# act-drive1.net
KiCad netlist of a schematic drawn in EAGLE
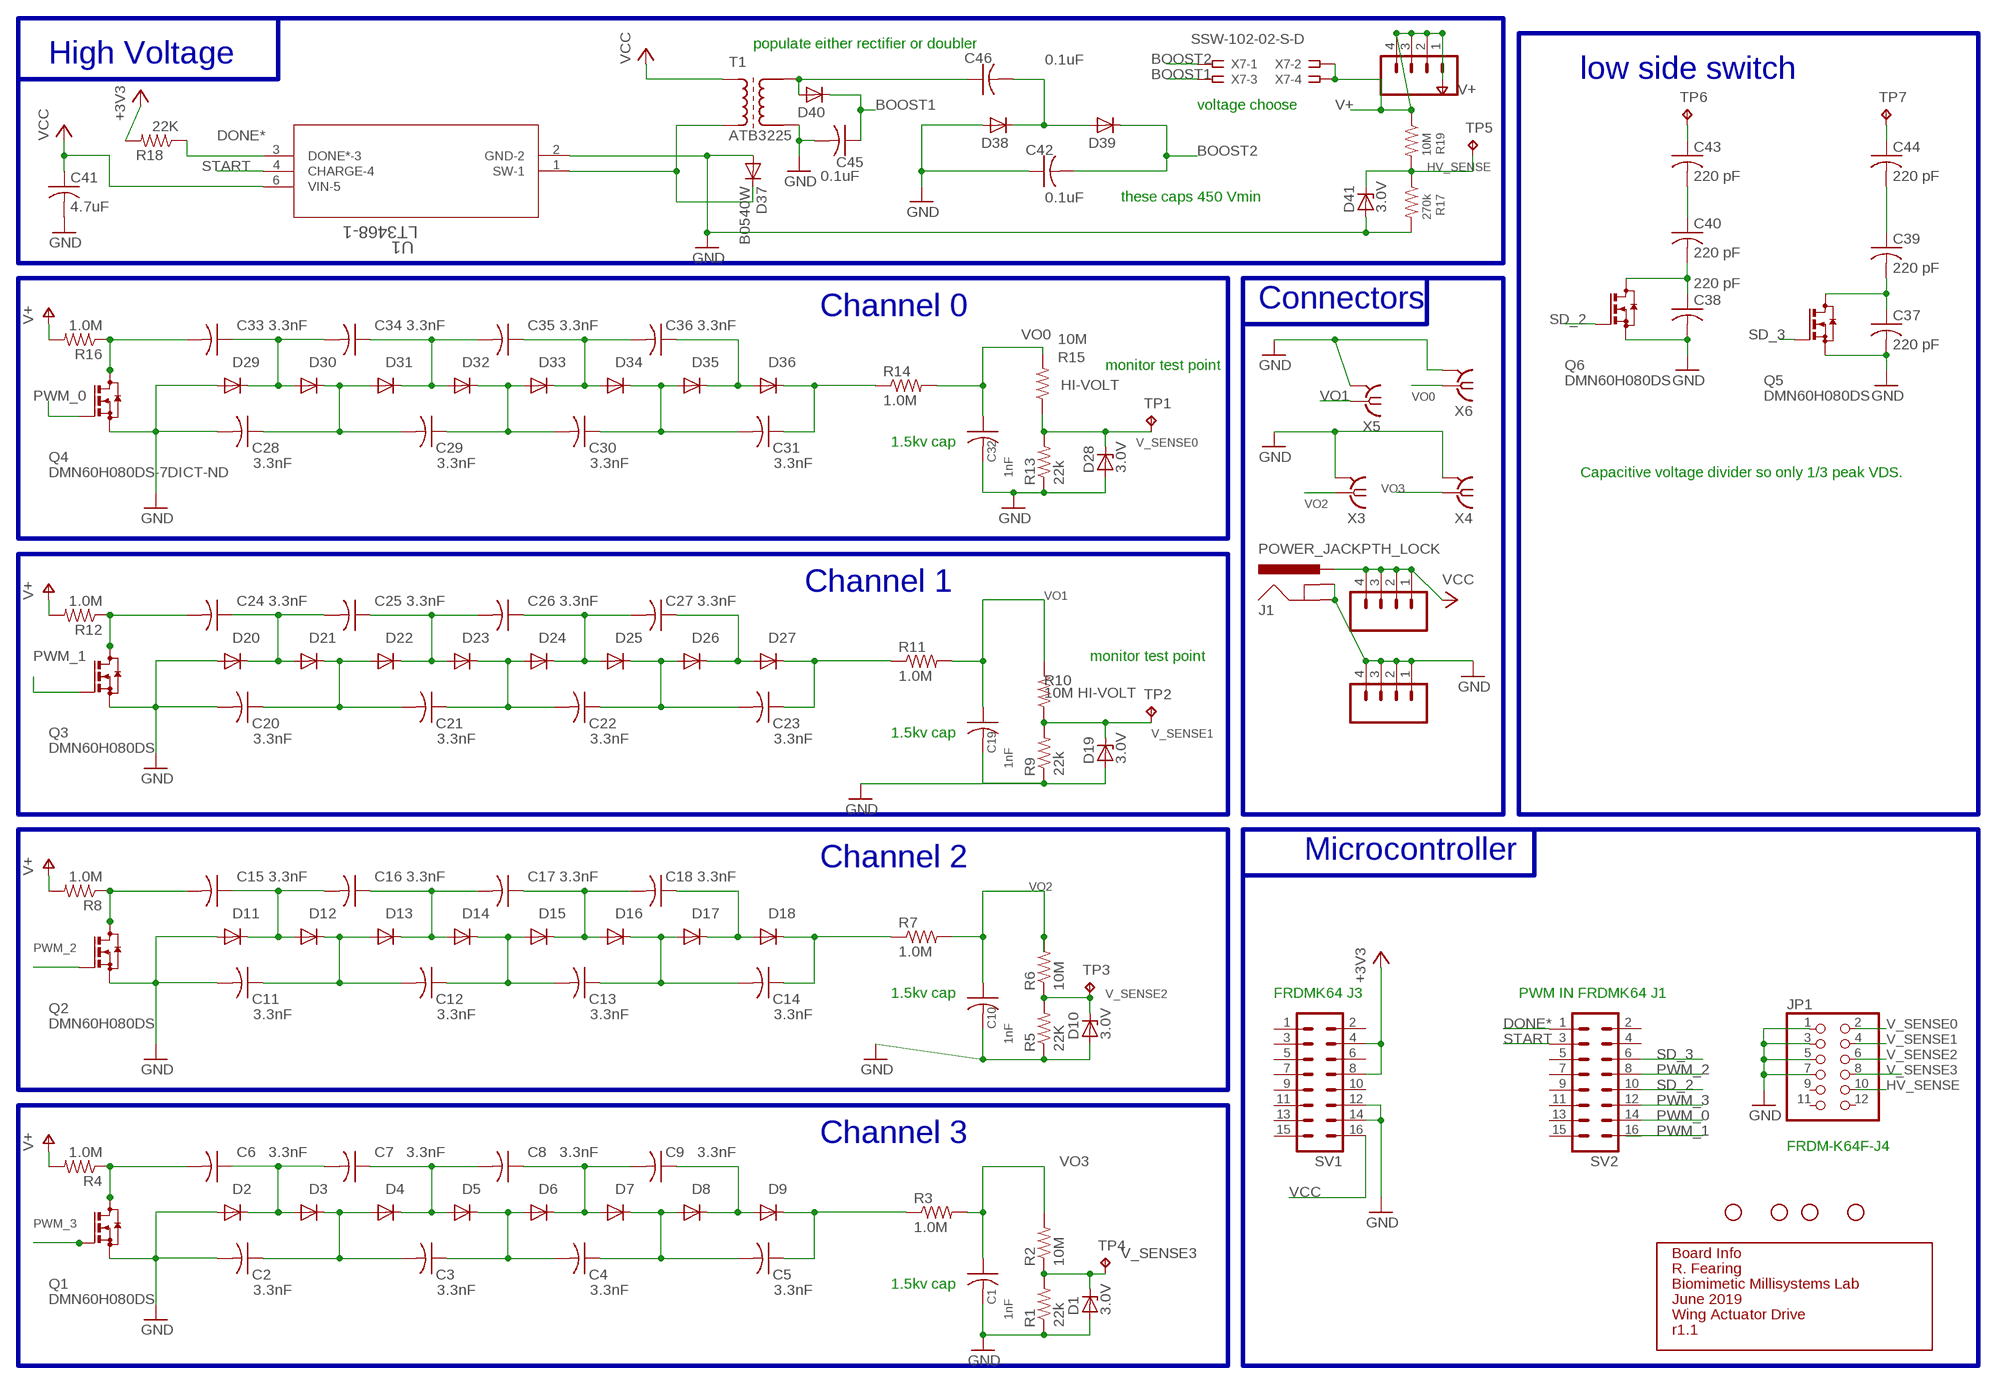
[diagram p0: schematic, sheet 1]

(export (version "E")
  (design (tool "Eeschema 10.0.6"))
  (components
    (comp (ref "C1")
      (value "1nF")
      (footprint "eagle-import:C1206")
      (libsource (lib "eagle-import") (part "C-USC1206"))
    )
    (comp (ref "C2")
      (value "3.3nF")
      (footprint "eagle-import:C0805K")
      (libsource (lib "eagle-import") (part "rcl_334_C-USC0805K"))
    )
    (comp (ref "C3")
      (value "3.3nF")
      (footprint "eagle-import:C0805K")
      (libsource (lib "eagle-import") (part "rcl_334_C-USC0805K"))
    )
    (comp (ref "C4")
      (value "3.3nF")
      (footprint "eagle-import:C0805K")
      (libsource (lib "eagle-import") (part "rcl_334_C-USC0805K"))
    )
    (comp (ref "C5")
      (value "3.3nF")
      (footprint "eagle-import:C0805K")
      (libsource (lib "eagle-import") (part "rcl_334_C-USC0805K"))
    )
    (comp (ref "C6")
      (value "3.3nF")
      (footprint "eagle-import:C0805K")
      (libsource (lib "eagle-import") (part "rcl_334_C-USC0805K"))
    )
    (comp (ref "C7")
      (value "3.3nF")
      (footprint "eagle-import:C0805K")
      (libsource (lib "eagle-import") (part "rcl_334_C-USC0805K"))
    )
    (comp (ref "C8")
      (value "3.3nF")
      (footprint "eagle-import:C0805K")
      (libsource (lib "eagle-import") (part "rcl_334_C-USC0805K"))
    )
    (comp (ref "C9")
      (value "3.3nF")
      (footprint "eagle-import:C0805K")
      (libsource (lib "eagle-import") (part "rcl_334_C-USC0805K"))
    )
    (comp (ref "C10")
      (value "1nF")
      (footprint "eagle-import:C1206")
      (libsource (lib "eagle-import") (part "C-USC1206"))
    )
    (comp (ref "C11")
      (value "3.3nF")
      (footprint "eagle-import:C0805K")
      (libsource (lib "eagle-import") (part "rcl_334_C-USC0805K"))
    )
    (comp (ref "C12")
      (value "3.3nF")
      (footprint "eagle-import:C0805K")
      (libsource (lib "eagle-import") (part "rcl_334_C-USC0805K"))
    )
    (comp (ref "C13")
      (value "3.3nF")
      (footprint "eagle-import:C0805K")
      (libsource (lib "eagle-import") (part "rcl_334_C-USC0805K"))
    )
    (comp (ref "C14")
      (value "3.3nF")
      (footprint "eagle-import:C0805K")
      (libsource (lib "eagle-import") (part "rcl_334_C-USC0805K"))
    )
    (comp (ref "C15")
      (value "3.3nF")
      (footprint "eagle-import:C0805K")
      (libsource (lib "eagle-import") (part "rcl_334_C-USC0805K"))
    )
    (comp (ref "C16")
      (value "3.3nF")
      (footprint "eagle-import:C0805K")
      (libsource (lib "eagle-import") (part "rcl_334_C-USC0805K"))
    )
    (comp (ref "C17")
      (value "3.3nF")
      (footprint "eagle-import:C0805K")
      (libsource (lib "eagle-import") (part "rcl_334_C-USC0805K"))
    )
    (comp (ref "C18")
      (value "3.3nF")
      (footprint "eagle-import:C0805K")
      (libsource (lib "eagle-import") (part "rcl_334_C-USC0805K"))
    )
    (comp (ref "C19")
      (value "1nF")
      (footprint "eagle-import:C1206")
      (libsource (lib "eagle-import") (part "C-USC1206"))
    )
    (comp (ref "C20")
      (value "3.3nF")
      (footprint "eagle-import:C0805K")
      (libsource (lib "eagle-import") (part "rcl_334_C-USC0805K"))
    )
    (comp (ref "C21")
      (value "3.3nF")
      (footprint "eagle-import:C0805K")
      (libsource (lib "eagle-import") (part "rcl_334_C-USC0805K"))
    )
    (comp (ref "C22")
      (value "3.3nF")
      (footprint "eagle-import:C0805K")
      (libsource (lib "eagle-import") (part "rcl_334_C-USC0805K"))
    )
    (comp (ref "C23")
      (value "3.3nF")
      (footprint "eagle-import:C0805K")
      (libsource (lib "eagle-import") (part "rcl_334_C-USC0805K"))
    )
    (comp (ref "C24")
      (value "3.3nF")
      (footprint "eagle-import:C0805K")
      (libsource (lib "eagle-import") (part "rcl_334_C-USC0805K"))
    )
    (comp (ref "C25")
      (value "3.3nF")
      (footprint "eagle-import:C0805K")
      (libsource (lib "eagle-import") (part "rcl_334_C-USC0805K"))
    )
    (comp (ref "C26")
      (value "3.3nF")
      (footprint "eagle-import:C0805K")
      (libsource (lib "eagle-import") (part "rcl_334_C-USC0805K"))
    )
    (comp (ref "C27")
      (value "3.3nF")
      (footprint "eagle-import:C0805K")
      (libsource (lib "eagle-import") (part "rcl_334_C-USC0805K"))
    )
    (comp (ref "C28")
      (value "3.3nF")
      (footprint "eagle-import:C0805K")
      (libsource (lib "eagle-import") (part "rcl_334_C-USC0805K"))
    )
    (comp (ref "C29")
      (value "3.3nF")
      (footprint "eagle-import:C0805K")
      (libsource (lib "eagle-import") (part "rcl_334_C-USC0805K"))
    )
    (comp (ref "C30")
      (value "3.3nF")
      (footprint "eagle-import:C0805K")
      (libsource (lib "eagle-import") (part "rcl_334_C-USC0805K"))
    )
    (comp (ref "C31")
      (value "3.3nF")
      (footprint "eagle-import:C0805K")
      (libsource (lib "eagle-import") (part "rcl_334_C-USC0805K"))
    )
    (comp (ref "C32")
      (value "1nF")
      (footprint "eagle-import:C1206")
      (libsource (lib "eagle-import") (part "C-USC1206"))
    )
    (comp (ref "C33")
      (value "3.3nF")
      (footprint "eagle-import:C0805K")
      (libsource (lib "eagle-import") (part "rcl_334_C-USC0805K"))
    )
    (comp (ref "C34")
      (value "3.3nF")
      (footprint "eagle-import:C0805K")
      (libsource (lib "eagle-import") (part "rcl_334_C-USC0805K"))
    )
    (comp (ref "C35")
      (value "3.3nF")
      (footprint "eagle-import:C0805K")
      (libsource (lib "eagle-import") (part "rcl_334_C-USC0805K"))
    )
    (comp (ref "C36")
      (value "3.3nF")
      (footprint "eagle-import:C0805K")
      (libsource (lib "eagle-import") (part "rcl_334_C-USC0805K"))
    )
    (comp (ref "C37")
      (value "220 pF")
      (footprint "eagle-import:C1206")
      (libsource (lib "eagle-import") (part "rcl_334_C-USC1206"))
    )
    (comp (ref "C38")
      (value "220 pF")
      (footprint "eagle-import:C1206")
      (libsource (lib "eagle-import") (part "rcl_334_C-USC1206"))
    )
    (comp (ref "C39")
      (value "220 pF")
      (footprint "eagle-import:C1206")
      (libsource (lib "eagle-import") (part "rcl_334_C-USC1206"))
    )
    (comp (ref "C40")
      (value "220 pF")
      (footprint "eagle-import:C1206")
      (libsource (lib "eagle-import") (part "rcl_334_C-USC1206"))
    )
    (comp (ref "C41")
      (value "4.7uF")
      (footprint "eagle-import:C1206")
      (libsource (lib "eagle-import") (part "C-USC1206"))
    )
    (comp (ref "C42")
      (value "0.1uF")
      (footprint "eagle-import:C1206")
      (libsource (lib "eagle-import") (part "rcl_334_C-USC1206"))
    )
    (comp (ref "C43")
      (value "220 pF")
      (footprint "eagle-import:C1206")
      (libsource (lib "eagle-import") (part "rcl_334_C-USC1206"))
    )
    (comp (ref "C44")
      (value "220 pF")
      (footprint "eagle-import:C1206")
      (libsource (lib "eagle-import") (part "rcl_334_C-USC1206"))
    )
    (comp (ref "C45")
      (value "0.1uF")
      (footprint "eagle-import:C1206")
      (libsource (lib "eagle-import") (part "rcl_334_C-USC1206"))
    )
    (comp (ref "C46")
      (value "0.1uF")
      (footprint "eagle-import:C1206")
      (libsource (lib "eagle-import") (part "rcl_334_C-USC1206"))
    )
    (comp (ref "D1")
      (value "3.0V")
      (footprint "eagle-import:SOD80C")
      (libsource (lib "eagle-import") (part "ZENER-DIODESOD80C"))
    )
    (comp (ref "D2")
      (value "DIODE-SOD323-W")
      (footprint "eagle-import:SOD323-W")
      (libsource (lib "eagle-import") (part "DIODE-SOD323-W"))
    )
    (comp (ref "D3")
      (value "DIODE-SOD323-W")
      (footprint "eagle-import:SOD323-W")
      (libsource (lib "eagle-import") (part "DIODE-SOD323-W"))
    )
    (comp (ref "D4")
      (value "DIODE-SOD323-W")
      (footprint "eagle-import:SOD323-W")
      (libsource (lib "eagle-import") (part "DIODE-SOD323-W"))
    )
    (comp (ref "D5")
      (value "DIODE-SOD323-W")
      (footprint "eagle-import:SOD323-W")
      (libsource (lib "eagle-import") (part "DIODE-SOD323-W"))
    )
    (comp (ref "D6")
      (value "DIODE-SOD323-W")
      (footprint "eagle-import:SOD323-W")
      (libsource (lib "eagle-import") (part "DIODE-SOD323-W"))
    )
    (comp (ref "D7")
      (value "DIODE-SOD323-W")
      (footprint "eagle-import:SOD323-W")
      (libsource (lib "eagle-import") (part "DIODE-SOD323-W"))
    )
    (comp (ref "D8")
      (value "DIODE-SOD323-W")
      (footprint "eagle-import:SOD323-W")
      (libsource (lib "eagle-import") (part "DIODE-SOD323-W"))
    )
    (comp (ref "D9")
      (value "DIODE-SOD323-W")
      (footprint "eagle-import:SOD323-W")
      (libsource (lib "eagle-import") (part "DIODE-SOD323-W"))
    )
    (comp (ref "D10")
      (value "3.0V")
      (footprint "eagle-import:SOD80C")
      (libsource (lib "eagle-import") (part "ZENER-DIODESOD80C"))
    )
    (comp (ref "D11")
      (value "DIODE-SOD323-W")
      (footprint "eagle-import:SOD323-W")
      (libsource (lib "eagle-import") (part "DIODE-SOD323-W"))
    )
    (comp (ref "D12")
      (value "DIODE-SOD323-W")
      (footprint "eagle-import:SOD323-W")
      (libsource (lib "eagle-import") (part "DIODE-SOD323-W"))
    )
    (comp (ref "D13")
      (value "DIODE-SOD323-W")
      (footprint "eagle-import:SOD323-W")
      (libsource (lib "eagle-import") (part "DIODE-SOD323-W"))
    )
    (comp (ref "D14")
      (value "DIODE-SOD323-W")
      (footprint "eagle-import:SOD323-W")
      (libsource (lib "eagle-import") (part "DIODE-SOD323-W"))
    )
    (comp (ref "D15")
      (value "DIODE-SOD323-W")
      (footprint "eagle-import:SOD323-W")
      (libsource (lib "eagle-import") (part "DIODE-SOD323-W"))
    )
    (comp (ref "D16")
      (value "DIODE-SOD323-W")
      (footprint "eagle-import:SOD323-W")
      (libsource (lib "eagle-import") (part "DIODE-SOD323-W"))
    )
    (comp (ref "D17")
      (value "DIODE-SOD323-W")
      (footprint "eagle-import:SOD323-W")
      (libsource (lib "eagle-import") (part "DIODE-SOD323-W"))
    )
    (comp (ref "D18")
      (value "DIODE-SOD323-W")
      (footprint "eagle-import:SOD323-W")
      (libsource (lib "eagle-import") (part "DIODE-SOD323-W"))
    )
    (comp (ref "D19")
      (value "3.0V")
      (footprint "eagle-import:SOD80C")
      (libsource (lib "eagle-import") (part "ZENER-DIODESOD80C"))
    )
    (comp (ref "D20")
      (value "DIODE-SOD323-W")
      (footprint "eagle-import:SOD323-W")
      (libsource (lib "eagle-import") (part "DIODE-SOD323-W"))
    )
    (comp (ref "D21")
      (value "DIODE-SOD323-W")
      (footprint "eagle-import:SOD323-W")
      (libsource (lib "eagle-import") (part "DIODE-SOD323-W"))
    )
    (comp (ref "D22")
      (value "DIODE-SOD323-W")
      (footprint "eagle-import:SOD323-W")
      (libsource (lib "eagle-import") (part "DIODE-SOD323-W"))
    )
    (comp (ref "D23")
      (value "DIODE-SOD323-W")
      (footprint "eagle-import:SOD323-W")
      (libsource (lib "eagle-import") (part "DIODE-SOD323-W"))
    )
    (comp (ref "D24")
      (value "DIODE-SOD323-W")
      (footprint "eagle-import:SOD323-W")
      (libsource (lib "eagle-import") (part "DIODE-SOD323-W"))
    )
    (comp (ref "D25")
      (value "DIODE-SOD323-W")
      (footprint "eagle-import:SOD323-W")
      (libsource (lib "eagle-import") (part "DIODE-SOD323-W"))
    )
    (comp (ref "D26")
      (value "DIODE-SOD323-W")
      (footprint "eagle-import:SOD323-W")
      (libsource (lib "eagle-import") (part "DIODE-SOD323-W"))
    )
    (comp (ref "D27")
      (value "DIODE-SOD323-W")
      (footprint "eagle-import:SOD323-W")
      (libsource (lib "eagle-import") (part "DIODE-SOD323-W"))
    )
    (comp (ref "D28")
      (value "3.0V")
      (footprint "eagle-import:SOD80C")
      (libsource (lib "eagle-import") (part "ZENER-DIODESOD80C"))
    )
    (comp (ref "D29")
      (value "DIODE-SOD323-W")
      (footprint "eagle-import:SOD323-W")
      (libsource (lib "eagle-import") (part "DIODE-SOD323-W"))
    )
    (comp (ref "D30")
      (value "DIODE-SOD323-W")
      (footprint "eagle-import:SOD323-W")
      (libsource (lib "eagle-import") (part "DIODE-SOD323-W"))
    )
    (comp (ref "D31")
      (value "DIODE-SOD323-W")
      (footprint "eagle-import:SOD323-W")
      (libsource (lib "eagle-import") (part "DIODE-SOD323-W"))
    )
    (comp (ref "D32")
      (value "DIODE-SOD323-W")
      (footprint "eagle-import:SOD323-W")
      (libsource (lib "eagle-import") (part "DIODE-SOD323-W"))
    )
    (comp (ref "D33")
      (value "DIODE-SOD323-W")
      (footprint "eagle-import:SOD323-W")
      (libsource (lib "eagle-import") (part "DIODE-SOD323-W"))
    )
    (comp (ref "D34")
      (value "DIODE-SOD323-W")
      (footprint "eagle-import:SOD323-W")
      (libsource (lib "eagle-import") (part "DIODE-SOD323-W"))
    )
    (comp (ref "D35")
      (value "DIODE-SOD323-W")
      (footprint "eagle-import:SOD323-W")
      (libsource (lib "eagle-import") (part "DIODE-SOD323-W"))
    )
    (comp (ref "D36")
      (value "DIODE-SOD323-W")
      (footprint "eagle-import:SOD323-W")
      (libsource (lib "eagle-import") (part "DIODE-SOD323-W"))
    )
    (comp (ref "D37")
      (value "B0540W")
      (footprint "eagle-import:SOD123")
      (libsource (lib "eagle-import") (part "DIODE-SOD123"))
    )
    (comp (ref "D38")
      (value "DIODE-SOD323-W")
      (footprint "eagle-import:SOD323-W")
      (libsource (lib "eagle-import") (part "DIODE-SOD323-W"))
    )
    (comp (ref "D39")
      (value "DIODE-SOD323-W")
      (footprint "eagle-import:SOD323-W")
      (libsource (lib "eagle-import") (part "DIODE-SOD323-W"))
    )
    (comp (ref "D40")
      (value "DIODE-SOD323-W")
      (footprint "eagle-import:SOD323-W")
      (libsource (lib "eagle-import") (part "DIODE-SOD323-W"))
    )
    (comp (ref "D41")
      (value "3.0V")
      (footprint "eagle-import:SOD80C")
      (libsource (lib "eagle-import") (part "ZENER-DIODESOD80C"))
    )
    (comp (ref "H1")
      (value "STAND-OFFTIGHT")
      (footprint "eagle-import:STAND-OFF-TIGHT")
      (libsource (lib "eagle-import") (part "STAND-OFFTIGHT"))
    )
    (comp (ref "H2")
      (value "STAND-OFFTIGHT")
      (footprint "eagle-import:STAND-OFF-TIGHT")
      (libsource (lib "eagle-import") (part "STAND-OFFTIGHT"))
    )
    (comp (ref "H3")
      (value "STAND-OFFTIGHT")
      (footprint "eagle-import:STAND-OFF-TIGHT")
      (libsource (lib "eagle-import") (part "STAND-OFFTIGHT"))
    )
    (comp (ref "H4")
      (value "STAND-OFFTIGHT")
      (footprint "eagle-import:STAND-OFF-TIGHT")
      (libsource (lib "eagle-import") (part "STAND-OFFTIGHT"))
    )
    (comp (ref "I1")
      (value "INFO")
      (footprint "eagle-import:INFO")
      (fields
        (field (name "AUTHOR") "R. Fearing")
        (field (name "DATE") "June 2019")
        (field (name "DESIGN") "Wing Actuator Drive")
        (field (name "ORGANIZATION") "Biomimetic Millisystems Lab")
        (field (name "REVISION") "r1.1")
      )
      (libsource (lib "eagle-import") (part "INFO"))
    )
    (comp (ref "J1")
      (value "POWER_JACKPTH_LOCK")
      (footprint "eagle-import:POWER_JACK_PTH_LOCK")
      (libsource (lib "eagle-import") (part "POWER_JACKPTH_LOCK"))
    )
    (comp (ref "JP1")
      (value "PINHD-2X6")
      (footprint "eagle-import:2X06")
      (libsource (lib "eagle-import") (part "PINHD-2X6"))
    )
    (comp (ref "JP2")
      (value "M04LOCK")
      (footprint "eagle-import:1X04_LOCK")
      (libsource (lib "eagle-import") (part "M04LOCK"))
    )
    (comp (ref "JP3")
      (value "M04LOCK")
      (footprint "eagle-import:1X04_LOCK")
      (libsource (lib "eagle-import") (part "M04LOCK"))
    )
    (comp (ref "JP4")
      (value "M04LOCK")
      (footprint "eagle-import:1X04_LOCK")
      (libsource (lib "eagle-import") (part "M04LOCK"))
    )
    (comp (ref "Q1")
      (value "BSS123")
      (footprint "eagle-import:SOT23")
      (fields (field (name "PART#") "DMN60H080DS"))
      (libsource (lib "eagle-import") (part "BSS123"))
    )
    (comp (ref "Q2")
      (value "BSS123")
      (footprint "eagle-import:SOT23")
      (fields (field (name "PART#") "DMN60H080DS"))
      (libsource (lib "eagle-import") (part "BSS123"))
    )
    (comp (ref "Q3")
      (value "BSS123")
      (footprint "eagle-import:SOT23")
      (fields (field (name "PART#") "DMN60H080DS"))
      (libsource (lib "eagle-import") (part "BSS123"))
    )
    (comp (ref "Q4")
      (value "BSS123")
      (footprint "eagle-import:SOT23")
      (fields (field (name "DIGIKEY") "DMN60H080DS-7DICT-ND "))
      (libsource (lib "eagle-import") (part "BSS123"))
    )
    (comp (ref "Q5")
      (value "BSS123")
      (footprint "eagle-import:SOT23")
      (fields (field (name "PART#") "DMN60H080DS"))
      (libsource (lib "eagle-import") (part "BSS123"))
    )
    (comp (ref "Q6")
      (value "BSS123")
      (footprint "eagle-import:SOT23")
      (fields (field (name "PART#") "DMN60H080DS"))
      (libsource (lib "eagle-import") (part "BSS123"))
    )
    (comp (ref "R1")
      (value "22k")
      (footprint "eagle-import:R1206")
      (libsource (lib "eagle-import") (part "R-US_R1206"))
    )
    (comp (ref "R2")
      (value "10M")
      (footprint "eagle-import:R2010")
      (libsource (lib "eagle-import") (part "R-US_R2010"))
    )
    (comp (ref "R3")
      (value "1.0M")
      (footprint "eagle-import:R1206")
      (libsource (lib "eagle-import") (part "R-US_R1206"))
    )
    (comp (ref "R4")
      (value "1.0M")
      (footprint "eagle-import:R1206")
      (libsource (lib "eagle-import") (part "R-US_R1206"))
    )
    (comp (ref "R5")
      (value "22K")
      (footprint "eagle-import:R1206")
      (libsource (lib "eagle-import") (part "R-US_R1206"))
    )
    (comp (ref "R6")
      (value "10M")
      (footprint "eagle-import:R2010")
      (libsource (lib "eagle-import") (part "R-US_R2010"))
    )
    (comp (ref "R7")
      (value "1.0M")
      (footprint "eagle-import:R1206")
      (libsource (lib "eagle-import") (part "R-US_R1206"))
    )
    (comp (ref "R8")
      (value "1.0M")
      (footprint "eagle-import:R1206")
      (libsource (lib "eagle-import") (part "R-US_R1206"))
    )
    (comp (ref "R9")
      (value "22k")
      (footprint "eagle-import:R1206")
      (libsource (lib "eagle-import") (part "R-US_R1206"))
    )
    (comp (ref "R10")
      (value "10M")
      (footprint "eagle-import:R2010")
      (libsource (lib "eagle-import") (part "R-US_R2010"))
    )
    (comp (ref "R11")
      (value "1.0M")
      (footprint "eagle-import:R1206")
      (libsource (lib "eagle-import") (part "R-US_R1206"))
    )
    (comp (ref "R12")
      (value "1.0M")
      (footprint "eagle-import:R1206")
      (libsource (lib "eagle-import") (part "R-US_R1206"))
    )
    (comp (ref "R13")
      (value "22k")
      (footprint "eagle-import:R1206")
      (libsource (lib "eagle-import") (part "R-US_R1206"))
    )
    (comp (ref "R14")
      (value "1.0M")
      (footprint "eagle-import:R1206")
      (libsource (lib "eagle-import") (part "R-US_R1206"))
    )
    (comp (ref "R15")
      (value "10M")
      (footprint "eagle-import:R2010")
      (libsource (lib "eagle-import") (part "R-US_R2010"))
    )
    (comp (ref "R16")
      (value "1.0M")
      (footprint "eagle-import:R1206")
      (libsource (lib "eagle-import") (part "R-US_R1206"))
    )
    (comp (ref "R17")
      (value "270k")
      (footprint "eagle-import:R1206")
      (libsource (lib "eagle-import") (part "R-US_R1206"))
    )
    (comp (ref "R18")
      (value "22K")
      (footprint "eagle-import:R1206")
      (libsource (lib "eagle-import") (part "resistor_348_R-US_R1206"))
    )
    (comp (ref "R19")
      (value "10M")
      (footprint "eagle-import:R1206")
      (libsource (lib "eagle-import") (part "R-US_R1206"))
    )
    (comp (ref "SV1")
      (value "ML16")
      (footprint "eagle-import:ML16")
      (libsource (lib "eagle-import") (part "ML16"))
    )
    (comp (ref "SV2")
      (value "ML16")
      (footprint "eagle-import:ML16")
      (libsource (lib "eagle-import") (part "ML16"))
    )
    (comp (ref "T1")
      (value "ATB3225")
      (footprint "eagle-import:XFMR3225")
      (libsource (lib "eagle-import") (part "ATB3225"))
    )
    (comp (ref "TP1")
      (value "TPTP10SQ")
      (footprint "eagle-import:TP10SQ")
      (libsource (lib "eagle-import") (part "TPTP10SQ"))
    )
    (comp (ref "TP2")
      (value "TPTP10SQ")
      (footprint "eagle-import:TP10SQ")
      (libsource (lib "eagle-import") (part "TPTP10SQ"))
    )
    (comp (ref "TP3")
      (value "TPTP10SQ")
      (footprint "eagle-import:TP10SQ")
      (libsource (lib "eagle-import") (part "TPTP10SQ"))
    )
    (comp (ref "TP4")
      (value "TPTP10SQ")
      (footprint "eagle-import:TP10SQ")
      (libsource (lib "eagle-import") (part "TPTP10SQ"))
    )
    (comp (ref "TP5")
      (value "TPTP20SQ")
      (footprint "eagle-import:TP20SQ")
      (libsource (lib "eagle-import") (part "TPTP20SQ"))
    )
    (comp (ref "TP6")
      (value "TPTP20SQ")
      (footprint "eagle-import:TP20SQ")
      (libsource (lib "eagle-import") (part "TPTP20SQ"))
    )
    (comp (ref "TP7")
      (value "TPTP20SQ")
      (footprint "eagle-import:TP20SQ")
      (libsource (lib "eagle-import") (part "TPTP20SQ"))
    )
    (comp (ref "U1")
      (value "LT3468-1")
      (footprint "eagle-import:TSOT-23_S5")
      (libsource (lib "eagle-import") (part "LT3468-1"))
    )
    (comp (ref "X3")
      (value "SMA-142-0701-801/806")
      (footprint "eagle-import:J502-ND-142-0701-801_806")
      (fields (field (name "MF") "JOHNSON COMPONENTS") (field (name "MPN") "142-0701-801"))
      (libsource (lib "eagle-import") (part "SMA-142-0701-801/806"))
    )
    (comp (ref "X4")
      (value "SMA-142-0701-801/806")
      (footprint "eagle-import:J502-ND-142-0701-801_806")
      (fields (field (name "MF") "JOHNSON COMPONENTS") (field (name "MPN") "142-0701-801"))
      (libsource (lib "eagle-import") (part "SMA-142-0701-801/806"))
    )
    (comp (ref "X5")
      (value "SMA-142-0701-801/806")
      (footprint "eagle-import:J502-ND-142-0701-801_806")
      (fields (field (name "MF") "JOHNSON COMPONENTS") (field (name "MPN") "142-0701-801"))
      (libsource (lib "eagle-import") (part "SMA-142-0701-801/806"))
    )
    (comp (ref "X6")
      (value "SMA-142-0701-801/806")
      (footprint "eagle-import:J502-ND-142-0701-801_806")
      (fields (field (name "MF") "JOHNSON COMPONENTS") (field (name "MPN") "142-0701-801"))
      (libsource (lib "eagle-import") (part "SMA-142-0701-801/806"))
    )
    (comp (ref "X7")
      (value "SSW-102-02-S-D")
      (footprint "eagle-import:SSW-102-02-S-D")
      (libsource (lib "eagle-import") (part "SSW-102-02-S-D"))
    )
  )
  (nets
    (net (code "3") (name "+3V3") (class "Default")
      (node (ref "R18") (pin "2") (pinfunction "2_2") (pintype "passive"))
      (node (ref "SV1") (pin "4") (pinfunction "4_4") (pintype "passive"))
      (node (ref "SV1") (pin "8") (pinfunction "8_8") (pintype "passive"))
    )
    (net (code "4") (name "/BOOST1") (class "Default")
      (node (ref "C45") (pin "1") (pinfunction "1_1") (pintype "passive"))
      (node (ref "D40") (pin "C") (pinfunction "C_C") (pintype "passive"))
      (node (ref "X7") (pin "3") (pinfunction "1_3") (pintype "passive"))
    )
    (net (code "5") (name "/BOOST2") (class "Default")
      (node (ref "C42") (pin "2") (pinfunction "2_2") (pintype "passive"))
      (node (ref "D39") (pin "C") (pinfunction "C_C") (pintype "passive"))
      (node (ref "X7") (pin "1") (pinfunction "1_1") (pintype "passive"))
    )
    (net (code "6") (name "/DONE*") (class "Default")
      (node (ref "R18") (pin "1") (pinfunction "1_1") (pintype "passive"))
      (node (ref "SV2") (pin "1") (pinfunction "1_1") (pintype "passive"))
      (node (ref "U1") (pin "3") (pinfunction "DONE*-3_3") (pintype "passive"))
    )
    (net (code "7") (name "/HV_SENSE") (class "Default")
      (node (ref "D41") (pin "C") (pinfunction "C_C") (pintype "passive"))
      (node (ref "JP1") (pin "10") (pinfunction "10_10") (pintype "passive"))
      (node (ref "R17") (pin "1") (pinfunction "1_1") (pintype "passive"))
      (node (ref "R19") (pin "2") (pinfunction "2_2") (pintype "passive"))
      (node (ref "TP5") (pin "TP") (pinfunction "TP_TP") (pintype "input"))
    )
    (net (code "8") (name "/PWM_0") (class "Default")
      (node (ref "Q4") (pin "1") (pinfunction "G_1") (pintype "passive"))
      (node (ref "SV2") (pin "14") (pinfunction "14_14") (pintype "passive"))
    )
    (net (code "9") (name "/PWM_1") (class "Default")
      (node (ref "Q3") (pin "1") (pinfunction "G_1") (pintype "passive"))
      (node (ref "SV2") (pin "16") (pinfunction "16_16") (pintype "passive"))
    )
    (net (code "10") (name "/PWM_2") (class "Default")
      (node (ref "Q2") (pin "1") (pinfunction "G_1") (pintype "passive"))
      (node (ref "SV2") (pin "8") (pinfunction "8_8") (pintype "passive"))
    )
    (net (code "11") (name "/PWM_3") (class "Default")
      (node (ref "Q1") (pin "1") (pinfunction "G_1") (pintype "passive"))
      (node (ref "SV2") (pin "12") (pinfunction "12_12") (pintype "passive"))
    )
    (net (code "12") (name "/SD_2") (class "Default")
      (node (ref "Q6") (pin "1") (pinfunction "G_1") (pintype "passive"))
      (node (ref "SV2") (pin "10") (pinfunction "10_10") (pintype "passive"))
    )
    (net (code "13") (name "/SD_3") (class "Default")
      (node (ref "Q5") (pin "1") (pinfunction "G_1") (pintype "passive"))
      (node (ref "SV2") (pin "6") (pinfunction "6_6") (pintype "passive"))
    )
    (net (code "14") (name "/START") (class "Default")
      (node (ref "SV2") (pin "3") (pinfunction "3_3") (pintype "passive"))
      (node (ref "U1") (pin "4") (pinfunction "CHARGE-4_4") (pintype "passive"))
    )
    (net (code "15") (name "/VO0") (class "Default")
      (node (ref "C32") (pin "1") (pinfunction "1_1") (pintype "passive"))
      (node (ref "R14") (pin "2") (pinfunction "2_2") (pintype "passive"))
      (node (ref "R15") (pin "2") (pinfunction "2_2") (pintype "passive"))
      (node (ref "X6") (pin "1") (pinfunction "1_1") (pintype "passive"))
    )
    (net (code "16") (name "/VO1") (class "Default")
      (node (ref "C19") (pin "1") (pinfunction "1_1") (pintype "passive"))
      (node (ref "R10") (pin "2") (pinfunction "2_2") (pintype "passive"))
      (node (ref "R11") (pin "2") (pinfunction "2_2") (pintype "passive"))
      (node (ref "X5") (pin "1") (pinfunction "1_1") (pintype "passive"))
    )
    (net (code "17") (name "/VO2") (class "Default")
      (node (ref "C10") (pin "1") (pinfunction "1_1") (pintype "passive"))
      (node (ref "R6") (pin "2") (pinfunction "2_2") (pintype "passive"))
      (node (ref "R7") (pin "2") (pinfunction "2_2") (pintype "passive"))
      (node (ref "X3") (pin "1") (pinfunction "1_1") (pintype "passive"))
    )
    (net (code "18") (name "/VO3") (class "Default")
      (node (ref "C1") (pin "1") (pinfunction "1_1") (pintype "passive"))
      (node (ref "R2") (pin "2") (pinfunction "2_2") (pintype "passive"))
      (node (ref "R3") (pin "2") (pinfunction "2_2") (pintype "passive"))
      (node (ref "X4") (pin "1") (pinfunction "1_1") (pintype "passive"))
    )
    (net (code "19") (name "/V_SENSE0") (class "Default")
      (node (ref "D28") (pin "C") (pinfunction "C_C") (pintype "passive"))
      (node (ref "JP1") (pin "2") (pinfunction "2_2") (pintype "passive"))
      (node (ref "R13") (pin "2") (pinfunction "2_2") (pintype "passive"))
      (node (ref "R15") (pin "1") (pinfunction "1_1") (pintype "passive"))
      (node (ref "TP1") (pin "TP") (pinfunction "TP_TP") (pintype "input"))
    )
    (net (code "20") (name "/V_SENSE1") (class "Default")
      (node (ref "D19") (pin "C") (pinfunction "C_C") (pintype "passive"))
      (node (ref "JP1") (pin "4") (pinfunction "4_4") (pintype "passive"))
      (node (ref "R10") (pin "1") (pinfunction "1_1") (pintype "passive"))
      (node (ref "R9") (pin "2") (pinfunction "2_2") (pintype "passive"))
      (node (ref "TP2") (pin "TP") (pinfunction "TP_TP") (pintype "input"))
    )
    (net (code "21") (name "/V_SENSE2") (class "Default")
      (node (ref "D10") (pin "C") (pinfunction "C_C") (pintype "passive"))
      (node (ref "JP1") (pin "6") (pinfunction "6_6") (pintype "passive"))
      (node (ref "R5") (pin "2") (pinfunction "2_2") (pintype "passive"))
      (node (ref "R6") (pin "1") (pinfunction "1_1") (pintype "passive"))
      (node (ref "TP3") (pin "TP") (pinfunction "TP_TP") (pintype "input"))
    )
    (net (code "22") (name "/V_SENSE3") (class "Default")
      (node (ref "D1") (pin "C") (pinfunction "C_C") (pintype "passive"))
      (node (ref "JP1") (pin "8") (pinfunction "8_8") (pintype "passive"))
      (node (ref "R1") (pin "2") (pinfunction "2_2") (pintype "passive"))
      (node (ref "R2") (pin "1") (pinfunction "1_1") (pintype "passive"))
      (node (ref "TP4") (pin "TP") (pinfunction "TP_TP") (pintype "input"))
    )
    (net (code "25") (name "GND") (class "Default")
      (node (ref "C1") (pin "2") (pinfunction "2_2") (pintype "passive"))
      (node (ref "C10") (pin "2") (pinfunction "2_2") (pintype "passive"))
      (node (ref "C11") (pin "2") (pinfunction "2_2") (pintype "passive"))
      (node (ref "C19") (pin "2") (pinfunction "2_2") (pintype "passive"))
      (node (ref "C2") (pin "2") (pinfunction "2_2") (pintype "passive"))
      (node (ref "C20") (pin "2") (pinfunction "2_2") (pintype "passive"))
      (node (ref "C28") (pin "2") (pinfunction "2_2") (pintype "passive"))
      (node (ref "C32") (pin "2") (pinfunction "2_2") (pintype "passive"))
      (node (ref "C37") (pin "2") (pinfunction "2_2") (pintype "passive"))
      (node (ref "C38") (pin "2") (pinfunction "2_2") (pintype "passive"))
      (node (ref "C41") (pin "2") (pinfunction "2_2") (pintype "passive"))
      (node (ref "C42") (pin "1") (pinfunction "1_1") (pintype "passive"))
      (node (ref "C45") (pin "2") (pinfunction "2_2") (pintype "passive"))
      (node (ref "D1") (pin "A") (pinfunction "A_A") (pintype "passive"))
      (node (ref "D10") (pin "A") (pinfunction "A_A") (pintype "passive"))
      (node (ref "D11") (pin "A") (pinfunction "A_A") (pintype "passive"))
      (node (ref "D19") (pin "A") (pinfunction "A_A") (pintype "passive"))
      (node (ref "D2") (pin "A") (pinfunction "A_A") (pintype "passive"))
      (node (ref "D20") (pin "A") (pinfunction "A_A") (pintype "passive"))
      (node (ref "D28") (pin "A") (pinfunction "A_A") (pintype "passive"))
      (node (ref "D29") (pin "A") (pinfunction "A_A") (pintype "passive"))
      (node (ref "D37") (pin "A") (pinfunction "A_A") (pintype "passive"))
      (node (ref "D38") (pin "A") (pinfunction "A_A") (pintype "passive"))
      (node (ref "D41") (pin "A") (pinfunction "A_A") (pintype "passive"))
      (node (ref "J1") (pin "GND") (pinfunction "GND_GND") (pintype "bidirectional"))
      (node (ref "J1") (pin "GNDBREAK") (pinfunction "GNDBREAK_GNDBREAK") (pintype "bidirectional"))
      (node (ref "JP1") (pin "1") (pinfunction "1_1") (pintype "passive"))
      (node (ref "JP1") (pin "3") (pinfunction "3_3") (pintype "passive"))
      (node (ref "JP1") (pin "5") (pinfunction "5_5") (pintype "passive"))
      (node (ref "JP1") (pin "7") (pinfunction "7_7") (pintype "passive"))
      (node (ref "JP2") (pin "1") (pinfunction "1_1") (pintype "passive"))
      (node (ref "JP2") (pin "2") (pinfunction "2_2") (pintype "passive"))
      (node (ref "JP2") (pin "3") (pinfunction "3_3") (pintype "passive"))
      (node (ref "JP2") (pin "4") (pinfunction "4_4") (pintype "passive"))
      (node (ref "Q1") (pin "2") (pinfunction "S_2") (pintype "passive"))
      (node (ref "Q2") (pin "2") (pinfunction "S_2") (pintype "passive"))
      (node (ref "Q3") (pin "2") (pinfunction "S_2") (pintype "passive"))
      (node (ref "Q4") (pin "2") (pinfunction "S_2") (pintype "passive"))
      (node (ref "Q5") (pin "2") (pinfunction "S_2") (pintype "passive"))
      (node (ref "Q6") (pin "2") (pinfunction "S_2") (pintype "passive"))
      (node (ref "R1") (pin "1") (pinfunction "1_1") (pintype "passive"))
      (node (ref "R13") (pin "1") (pinfunction "1_1") (pintype "passive"))
      (node (ref "R17") (pin "2") (pinfunction "2_2") (pintype "passive"))
      (node (ref "R5") (pin "1") (pinfunction "1_1") (pintype "passive"))
      (node (ref "R9") (pin "1") (pinfunction "1_1") (pintype "passive"))
      (node (ref "SV1") (pin "12") (pinfunction "12_12") (pintype "passive"))
      (node (ref "SV1") (pin "14") (pinfunction "14_14") (pintype "passive"))
      (node (ref "T1") (pin "S3") (pinfunction "S3_S3") (pintype "passive"))
      (node (ref "U1") (pin "2") (pinfunction "GND-2_2") (pintype "passive"))
      (node (ref "X3") (pin "G@1") (pinfunction "2_G@1") (pintype "passive"))
      (node (ref "X3") (pin "G@2") (pinfunction "2_G@2") (pintype "passive"))
      (node (ref "X3") (pin "G@3") (pinfunction "2_G@3") (pintype "passive"))
      (node (ref "X3") (pin "G@4") (pinfunction "2_G@4") (pintype "passive"))
      (node (ref "X4") (pin "G@1") (pinfunction "2_G@1") (pintype "passive"))
      (node (ref "X4") (pin "G@2") (pinfunction "2_G@2") (pintype "passive"))
      (node (ref "X4") (pin "G@3") (pinfunction "2_G@3") (pintype "passive"))
      (node (ref "X4") (pin "G@4") (pinfunction "2_G@4") (pintype "passive"))
      (node (ref "X5") (pin "G@1") (pinfunction "2_G@1") (pintype "passive"))
      (node (ref "X5") (pin "G@2") (pinfunction "2_G@2") (pintype "passive"))
      (node (ref "X5") (pin "G@3") (pinfunction "2_G@3") (pintype "passive"))
      (node (ref "X5") (pin "G@4") (pinfunction "2_G@4") (pintype "passive"))
      (node (ref "X6") (pin "G@1") (pinfunction "2_G@1") (pintype "passive"))
      (node (ref "X6") (pin "G@2") (pinfunction "2_G@2") (pintype "passive"))
      (node (ref "X6") (pin "G@3") (pinfunction "2_G@3") (pintype "passive"))
      (node (ref "X6") (pin "G@4") (pinfunction "2_G@4") (pintype "passive"))
    )
    (net (code "26") (name "Net-(C2-Pad1)") (class "Default")
      (node (ref "C2") (pin "1") (pinfunction "1_1") (pintype "passive"))
      (node (ref "C3") (pin "2") (pinfunction "2_2") (pintype "passive"))
      (node (ref "D3") (pin "C") (pinfunction "C_C") (pintype "passive"))
      (node (ref "D4") (pin "A") (pinfunction "A_A") (pintype "passive"))
    )
    (net (code "27") (name "Net-(C3-Pad1)") (class "Default")
      (node (ref "C3") (pin "1") (pinfunction "1_1") (pintype "passive"))
      (node (ref "C4") (pin "2") (pinfunction "2_2") (pintype "passive"))
      (node (ref "D5") (pin "C") (pinfunction "C_C") (pintype "passive"))
      (node (ref "D6") (pin "A") (pinfunction "A_A") (pintype "passive"))
    )
    (net (code "28") (name "Net-(C4-Pad1)") (class "Default")
      (node (ref "C4") (pin "1") (pinfunction "1_1") (pintype "passive"))
      (node (ref "C5") (pin "2") (pinfunction "2_2") (pintype "passive"))
      (node (ref "D7") (pin "C") (pinfunction "C_C") (pintype "passive"))
      (node (ref "D8") (pin "A") (pinfunction "A_A") (pintype "passive"))
    )
    (net (code "29") (name "Net-(C5-Pad1)") (class "Default")
      (node (ref "C5") (pin "1") (pinfunction "1_1") (pintype "passive"))
      (node (ref "D9") (pin "C") (pinfunction "C_C") (pintype "passive"))
      (node (ref "R3") (pin "1") (pinfunction "1_1") (pintype "passive"))
    )
    (net (code "30") (name "Net-(C6-Pad1)") (class "Default")
      (node (ref "C6") (pin "1") (pinfunction "1_1") (pintype "passive"))
      (node (ref "C7") (pin "2") (pinfunction "2_2") (pintype "passive"))
      (node (ref "D2") (pin "C") (pinfunction "C_C") (pintype "passive"))
      (node (ref "D3") (pin "A") (pinfunction "A_A") (pintype "passive"))
    )
    (net (code "31") (name "Net-(C7-Pad1)") (class "Default")
      (node (ref "C7") (pin "1") (pinfunction "1_1") (pintype "passive"))
      (node (ref "C8") (pin "2") (pinfunction "2_2") (pintype "passive"))
      (node (ref "D4") (pin "C") (pinfunction "C_C") (pintype "passive"))
      (node (ref "D5") (pin "A") (pinfunction "A_A") (pintype "passive"))
    )
    (net (code "32") (name "Net-(C8-Pad1)") (class "Default")
      (node (ref "C8") (pin "1") (pinfunction "1_1") (pintype "passive"))
      (node (ref "C9") (pin "2") (pinfunction "2_2") (pintype "passive"))
      (node (ref "D6") (pin "C") (pinfunction "C_C") (pintype "passive"))
      (node (ref "D7") (pin "A") (pinfunction "A_A") (pintype "passive"))
    )
    (net (code "33") (name "Net-(C9-Pad1)") (class "Default")
      (node (ref "C9") (pin "1") (pinfunction "1_1") (pintype "passive"))
      (node (ref "D8") (pin "C") (pinfunction "C_C") (pintype "passive"))
      (node (ref "D9") (pin "A") (pinfunction "A_A") (pintype "passive"))
    )
    (net (code "34") (name "Net-(C11-Pad1)") (class "Default")
      (node (ref "C11") (pin "1") (pinfunction "1_1") (pintype "passive"))
      (node (ref "C12") (pin "2") (pinfunction "2_2") (pintype "passive"))
      (node (ref "D12") (pin "C") (pinfunction "C_C") (pintype "passive"))
      (node (ref "D13") (pin "A") (pinfunction "A_A") (pintype "passive"))
    )
    (net (code "35") (name "Net-(C12-Pad1)") (class "Default")
      (node (ref "C12") (pin "1") (pinfunction "1_1") (pintype "passive"))
      (node (ref "C13") (pin "2") (pinfunction "2_2") (pintype "passive"))
      (node (ref "D14") (pin "C") (pinfunction "C_C") (pintype "passive"))
      (node (ref "D15") (pin "A") (pinfunction "A_A") (pintype "passive"))
    )
    (net (code "36") (name "Net-(C13-Pad1)") (class "Default")
      (node (ref "C13") (pin "1") (pinfunction "1_1") (pintype "passive"))
      (node (ref "C14") (pin "2") (pinfunction "2_2") (pintype "passive"))
      (node (ref "D16") (pin "C") (pinfunction "C_C") (pintype "passive"))
      (node (ref "D17") (pin "A") (pinfunction "A_A") (pintype "passive"))
    )
    (net (code "37") (name "Net-(C14-Pad1)") (class "Default")
      (node (ref "C14") (pin "1") (pinfunction "1_1") (pintype "passive"))
      (node (ref "D18") (pin "C") (pinfunction "C_C") (pintype "passive"))
      (node (ref "R7") (pin "1") (pinfunction "1_1") (pintype "passive"))
    )
    (net (code "38") (name "Net-(C15-Pad1)") (class "Default")
      (node (ref "C15") (pin "1") (pinfunction "1_1") (pintype "passive"))
      (node (ref "C16") (pin "2") (pinfunction "2_2") (pintype "passive"))
      (node (ref "D11") (pin "C") (pinfunction "C_C") (pintype "passive"))
      (node (ref "D12") (pin "A") (pinfunction "A_A") (pintype "passive"))
    )
    (net (code "39") (name "Net-(C16-Pad1)") (class "Default")
      (node (ref "C16") (pin "1") (pinfunction "1_1") (pintype "passive"))
      (node (ref "C17") (pin "2") (pinfunction "2_2") (pintype "passive"))
      (node (ref "D13") (pin "C") (pinfunction "C_C") (pintype "passive"))
      (node (ref "D14") (pin "A") (pinfunction "A_A") (pintype "passive"))
    )
    (net (code "40") (name "Net-(C17-Pad1)") (class "Default")
      (node (ref "C17") (pin "1") (pinfunction "1_1") (pintype "passive"))
      (node (ref "C18") (pin "2") (pinfunction "2_2") (pintype "passive"))
      (node (ref "D15") (pin "C") (pinfunction "C_C") (pintype "passive"))
      (node (ref "D16") (pin "A") (pinfunction "A_A") (pintype "passive"))
    )
    (net (code "41") (name "Net-(C18-Pad1)") (class "Default")
      (node (ref "C18") (pin "1") (pinfunction "1_1") (pintype "passive"))
      (node (ref "D17") (pin "C") (pinfunction "C_C") (pintype "passive"))
      (node (ref "D18") (pin "A") (pinfunction "A_A") (pintype "passive"))
    )
    (net (code "42") (name "Net-(C20-Pad1)") (class "Default")
      (node (ref "C20") (pin "1") (pinfunction "1_1") (pintype "passive"))
      (node (ref "C21") (pin "2") (pinfunction "2_2") (pintype "passive"))
      (node (ref "D21") (pin "C") (pinfunction "C_C") (pintype "passive"))
      (node (ref "D22") (pin "A") (pinfunction "A_A") (pintype "passive"))
    )
    (net (code "43") (name "Net-(C21-Pad1)") (class "Default")
      (node (ref "C21") (pin "1") (pinfunction "1_1") (pintype "passive"))
      (node (ref "C22") (pin "2") (pinfunction "2_2") (pintype "passive"))
      (node (ref "D23") (pin "C") (pinfunction "C_C") (pintype "passive"))
      (node (ref "D24") (pin "A") (pinfunction "A_A") (pintype "passive"))
    )
    (net (code "44") (name "Net-(C22-Pad1)") (class "Default")
      (node (ref "C22") (pin "1") (pinfunction "1_1") (pintype "passive"))
      (node (ref "C23") (pin "2") (pinfunction "2_2") (pintype "passive"))
      (node (ref "D25") (pin "C") (pinfunction "C_C") (pintype "passive"))
      (node (ref "D26") (pin "A") (pinfunction "A_A") (pintype "passive"))
    )
    (net (code "45") (name "Net-(C23-Pad1)") (class "Default")
      (node (ref "C23") (pin "1") (pinfunction "1_1") (pintype "passive"))
      (node (ref "D27") (pin "C") (pinfunction "C_C") (pintype "passive"))
      (node (ref "R11") (pin "1") (pinfunction "1_1") (pintype "passive"))
    )
    (net (code "46") (name "Net-(C24-Pad1)") (class "Default")
      (node (ref "C24") (pin "1") (pinfunction "1_1") (pintype "passive"))
      (node (ref "C25") (pin "2") (pinfunction "2_2") (pintype "passive"))
      (node (ref "D20") (pin "C") (pinfunction "C_C") (pintype "passive"))
      (node (ref "D21") (pin "A") (pinfunction "A_A") (pintype "passive"))
    )
    (net (code "47") (name "Net-(C25-Pad1)") (class "Default")
      (node (ref "C25") (pin "1") (pinfunction "1_1") (pintype "passive"))
      (node (ref "C26") (pin "2") (pinfunction "2_2") (pintype "passive"))
      (node (ref "D22") (pin "C") (pinfunction "C_C") (pintype "passive"))
      (node (ref "D23") (pin "A") (pinfunction "A_A") (pintype "passive"))
    )
    (net (code "48") (name "Net-(C26-Pad1)") (class "Default")
      (node (ref "C26") (pin "1") (pinfunction "1_1") (pintype "passive"))
      (node (ref "C27") (pin "2") (pinfunction "2_2") (pintype "passive"))
      (node (ref "D24") (pin "C") (pinfunction "C_C") (pintype "passive"))
      (node (ref "D25") (pin "A") (pinfunction "A_A") (pintype "passive"))
    )
    (net (code "49") (name "Net-(C27-Pad1)") (class "Default")
      (node (ref "C27") (pin "1") (pinfunction "1_1") (pintype "passive"))
      (node (ref "D26") (pin "C") (pinfunction "C_C") (pintype "passive"))
      (node (ref "D27") (pin "A") (pinfunction "A_A") (pintype "passive"))
    )
    (net (code "50") (name "Net-(C28-Pad1)") (class "Default")
      (node (ref "C28") (pin "1") (pinfunction "1_1") (pintype "passive"))
      (node (ref "C29") (pin "2") (pinfunction "2_2") (pintype "passive"))
      (node (ref "D30") (pin "C") (pinfunction "C_C") (pintype "passive"))
      (node (ref "D31") (pin "A") (pinfunction "A_A") (pintype "passive"))
    )
    (net (code "51") (name "Net-(C29-Pad1)") (class "Default")
      (node (ref "C29") (pin "1") (pinfunction "1_1") (pintype "passive"))
      (node (ref "C30") (pin "2") (pinfunction "2_2") (pintype "passive"))
      (node (ref "D32") (pin "C") (pinfunction "C_C") (pintype "passive"))
      (node (ref "D33") (pin "A") (pinfunction "A_A") (pintype "passive"))
    )
    (net (code "52") (name "Net-(C30-Pad1)") (class "Default")
      (node (ref "C30") (pin "1") (pinfunction "1_1") (pintype "passive"))
      (node (ref "C31") (pin "2") (pinfunction "2_2") (pintype "passive"))
      (node (ref "D34") (pin "C") (pinfunction "C_C") (pintype "passive"))
      (node (ref "D35") (pin "A") (pinfunction "A_A") (pintype "passive"))
    )
    (net (code "53") (name "Net-(C31-Pad1)") (class "Default")
      (node (ref "C31") (pin "1") (pinfunction "1_1") (pintype "passive"))
      (node (ref "D36") (pin "C") (pinfunction "C_C") (pintype "passive"))
      (node (ref "R14") (pin "1") (pinfunction "1_1") (pintype "passive"))
    )
    (net (code "54") (name "Net-(C33-Pad1)") (class "Default")
      (node (ref "C33") (pin "1") (pinfunction "1_1") (pintype "passive"))
      (node (ref "C34") (pin "2") (pinfunction "2_2") (pintype "passive"))
      (node (ref "D29") (pin "C") (pinfunction "C_C") (pintype "passive"))
      (node (ref "D30") (pin "A") (pinfunction "A_A") (pintype "passive"))
    )
    (net (code "55") (name "Net-(C34-Pad1)") (class "Default")
      (node (ref "C34") (pin "1") (pinfunction "1_1") (pintype "passive"))
      (node (ref "C35") (pin "2") (pinfunction "2_2") (pintype "passive"))
      (node (ref "D31") (pin "C") (pinfunction "C_C") (pintype "passive"))
      (node (ref "D32") (pin "A") (pinfunction "A_A") (pintype "passive"))
    )
    (net (code "56") (name "Net-(C35-Pad1)") (class "Default")
      (node (ref "C35") (pin "1") (pinfunction "1_1") (pintype "passive"))
      (node (ref "C36") (pin "2") (pinfunction "2_2") (pintype "passive"))
      (node (ref "D33") (pin "C") (pinfunction "C_C") (pintype "passive"))
      (node (ref "D34") (pin "A") (pinfunction "A_A") (pintype "passive"))
    )
    (net (code "57") (name "Net-(C36-Pad1)") (class "Default")
      (node (ref "C36") (pin "1") (pinfunction "1_1") (pintype "passive"))
      (node (ref "D35") (pin "C") (pinfunction "C_C") (pintype "passive"))
      (node (ref "D36") (pin "A") (pinfunction "A_A") (pintype "passive"))
    )
    (net (code "58") (name "Net-(C39-Pad1)") (class "Default")
      (node (ref "C39") (pin "1") (pinfunction "1_1") (pintype "passive"))
      (node (ref "C44") (pin "2") (pinfunction "2_2") (pintype "passive"))
    )
    (net (code "59") (name "Net-(C40-Pad1)") (class "Default")
      (node (ref "C40") (pin "1") (pinfunction "1_1") (pintype "passive"))
      (node (ref "C43") (pin "2") (pinfunction "2_2") (pintype "passive"))
    )
    (net (code "60") (name "Net-(C43-Pad1)") (class "Default")
      (node (ref "C43") (pin "1") (pinfunction "1_1") (pintype "passive"))
      (node (ref "TP6") (pin "TP") (pinfunction "TP_TP") (pintype "input"))
    )
    (net (code "61") (name "Net-(C44-Pad1)") (class "Default")
      (node (ref "C44") (pin "1") (pinfunction "1_1") (pintype "passive"))
      (node (ref "TP7") (pin "TP") (pinfunction "TP_TP") (pintype "input"))
    )
    (net (code "62") (name "Net-(C46-Pad1)") (class "Default")
      (node (ref "C46") (pin "1") (pinfunction "1_1") (pintype "passive"))
      (node (ref "D40") (pin "A") (pinfunction "A_A") (pintype "passive"))
      (node (ref "T1") (pin "S2") (pinfunction "S2_S2") (pintype "passive"))
    )
    (net (code "63") (name "Net-(C46-Pad2)") (class "Default")
      (node (ref "C46") (pin "2") (pinfunction "2_2") (pintype "passive"))
      (node (ref "D38") (pin "C") (pinfunction "C_C") (pintype "passive"))
      (node (ref "D39") (pin "A") (pinfunction "A_A") (pintype "passive"))
    )
    (net (code "64") (name "Net-(Q1-D)") (class "Default")
      (node (ref "C6") (pin "2") (pinfunction "2_2") (pintype "passive"))
      (node (ref "Q1") (pin "3") (pinfunction "D_3") (pintype "passive"))
      (node (ref "R4") (pin "1") (pinfunction "1_1") (pintype "passive"))
    )
    (net (code "65") (name "Net-(Q2-D)") (class "Default")
      (node (ref "C15") (pin "2") (pinfunction "2_2") (pintype "passive"))
      (node (ref "Q2") (pin "3") (pinfunction "D_3") (pintype "passive"))
      (node (ref "R8") (pin "1") (pinfunction "1_1") (pintype "passive"))
    )
    (net (code "66") (name "Net-(Q3-D)") (class "Default")
      (node (ref "C24") (pin "2") (pinfunction "2_2") (pintype "passive"))
      (node (ref "Q3") (pin "3") (pinfunction "D_3") (pintype "passive"))
      (node (ref "R12") (pin "1") (pinfunction "1_1") (pintype "passive"))
    )
    (net (code "67") (name "Net-(Q4-D)") (class "Default")
      (node (ref "C33") (pin "2") (pinfunction "2_2") (pintype "passive"))
      (node (ref "Q4") (pin "3") (pinfunction "D_3") (pintype "passive"))
      (node (ref "R16") (pin "1") (pinfunction "1_1") (pintype "passive"))
    )
    (net (code "68") (name "Net-(Q5-D)") (class "Default")
      (node (ref "C37") (pin "1") (pinfunction "1_1") (pintype "passive"))
      (node (ref "C39") (pin "2") (pinfunction "2_2") (pintype "passive"))
      (node (ref "Q5") (pin "3") (pinfunction "D_3") (pintype "passive"))
    )
    (net (code "69") (name "Net-(Q6-D)") (class "Default")
      (node (ref "C38") (pin "1") (pinfunction "1_1") (pintype "passive"))
      (node (ref "C40") (pin "2") (pinfunction "2_2") (pintype "passive"))
      (node (ref "Q6") (pin "3") (pinfunction "D_3") (pintype "passive"))
    )
    (net (code "70") (name "Net-(U1-SW-1)") (class "Default")
      (node (ref "D37") (pin "C") (pinfunction "C_C") (pintype "passive"))
      (node (ref "T1") (pin "P4") (pinfunction "P4_P4") (pintype "passive"))
      (node (ref "U1") (pin "1") (pinfunction "SW-1_1") (pintype "passive"))
    )
    (net (code "71") (name "V+") (class "Default")
      (node (ref "JP4") (pin "1") (pinfunction "1_1") (pintype "passive"))
      (node (ref "JP4") (pin "2") (pinfunction "2_2") (pintype "passive"))
      (node (ref "JP4") (pin "3") (pinfunction "3_3") (pintype "passive"))
      (node (ref "JP4") (pin "4") (pinfunction "4_4") (pintype "passive"))
      (node (ref "R12") (pin "2") (pinfunction "2_2") (pintype "passive"))
      (node (ref "R16") (pin "2") (pinfunction "2_2") (pintype "passive"))
      (node (ref "R19") (pin "1") (pinfunction "1_1") (pintype "passive"))
      (node (ref "R4") (pin "2") (pinfunction "2_2") (pintype "passive"))
      (node (ref "R8") (pin "2") (pinfunction "2_2") (pintype "passive"))
      (node (ref "X7") (pin "2") (pinfunction "1_2") (pintype "passive"))
      (node (ref "X7") (pin "4") (pinfunction "1_4") (pintype "passive"))
    )
    (net (code "72") (name "VCC") (class "Default")
      (node (ref "C41") (pin "1") (pinfunction "1_1") (pintype "passive"))
      (node (ref "J1") (pin "PWR") (pinfunction "PWR_PWR") (pintype "bidirectional"))
      (node (ref "JP3") (pin "1") (pinfunction "1_1") (pintype "passive"))
      (node (ref "JP3") (pin "2") (pinfunction "2_2") (pintype "passive"))
      (node (ref "JP3") (pin "3") (pinfunction "3_3") (pintype "passive"))
      (node (ref "JP3") (pin "4") (pinfunction "4_4") (pintype "passive"))
      (node (ref "SV1") (pin "16") (pinfunction "16_16") (pintype "passive"))
      (node (ref "T1") (pin "P1") (pinfunction "P1_P1") (pintype "passive"))
      (node (ref "U1") (pin "6") (pinfunction "VIN-5_6") (pintype "passive"))
    )
    (net (code "73") (name "unconnected-(JP1-Pad9)") (class "Default")
      (node (ref "JP1") (pin "9") (pinfunction "9_9") (pintype "passive"))
    )
    (net (code "74") (name "unconnected-(JP1-Pad11)") (class "Default")
      (node (ref "JP1") (pin "11") (pinfunction "11_11") (pintype "passive"))
    )
    (net (code "75") (name "unconnected-(JP1-Pad12)") (class "Default")
      (node (ref "JP1") (pin "12") (pinfunction "12_12") (pintype "passive"))
    )
    (net (code "76") (name "unconnected-(SV1-Pad1)") (class "Default")
      (node (ref "SV1") (pin "1") (pinfunction "1_1") (pintype "passive"))
    )
    (net (code "77") (name "unconnected-(SV1-Pad2)") (class "Default")
      (node (ref "SV1") (pin "2") (pinfunction "2_2") (pintype "passive"))
    )
    (net (code "78") (name "unconnected-(SV1-Pad3)") (class "Default")
      (node (ref "SV1") (pin "3") (pinfunction "3_3") (pintype "passive"))
    )
    (net (code "79") (name "unconnected-(SV1-Pad5)") (class "Default")
      (node (ref "SV1") (pin "5") (pinfunction "5_5") (pintype "passive"))
    )
    (net (code "80") (name "unconnected-(SV1-Pad6)") (class "Default")
      (node (ref "SV1") (pin "6") (pinfunction "6_6") (pintype "passive"))
    )
    (net (code "81") (name "unconnected-(SV1-Pad7)") (class "Default")
      (node (ref "SV1") (pin "7") (pinfunction "7_7") (pintype "passive"))
    )
    (net (code "82") (name "unconnected-(SV1-Pad9)") (class "Default")
      (node (ref "SV1") (pin "9") (pinfunction "9_9") (pintype "passive"))
    )
    (net (code "83") (name "unconnected-(SV1-Pad10)") (class "Default")
      (node (ref "SV1") (pin "10") (pinfunction "10_10") (pintype "passive"))
    )
    (net (code "84") (name "unconnected-(SV1-Pad11)") (class "Default")
      (node (ref "SV1") (pin "11") (pinfunction "11_11") (pintype "passive"))
    )
    (net (code "85") (name "unconnected-(SV1-Pad13)") (class "Default")
      (node (ref "SV1") (pin "13") (pinfunction "13_13") (pintype "passive"))
    )
    (net (code "86") (name "unconnected-(SV1-Pad15)") (class "Default")
      (node (ref "SV1") (pin "15") (pinfunction "15_15") (pintype "passive"))
    )
    (net (code "87") (name "unconnected-(SV2-Pad2)") (class "Default")
      (node (ref "SV2") (pin "2") (pinfunction "2_2") (pintype "passive"))
    )
    (net (code "88") (name "unconnected-(SV2-Pad4)") (class "Default")
      (node (ref "SV2") (pin "4") (pinfunction "4_4") (pintype "passive"))
    )
    (net (code "89") (name "unconnected-(SV2-Pad5)") (class "Default")
      (node (ref "SV2") (pin "5") (pinfunction "5_5") (pintype "passive"))
    )
    (net (code "90") (name "unconnected-(SV2-Pad7)") (class "Default")
      (node (ref "SV2") (pin "7") (pinfunction "7_7") (pintype "passive"))
    )
    (net (code "91") (name "unconnected-(SV2-Pad9)") (class "Default")
      (node (ref "SV2") (pin "9") (pinfunction "9_9") (pintype "passive"))
    )
    (net (code "92") (name "unconnected-(SV2-Pad11)") (class "Default")
      (node (ref "SV2") (pin "11") (pinfunction "11_11") (pintype "passive"))
    )
    (net (code "93") (name "unconnected-(SV2-Pad13)") (class "Default")
      (node (ref "SV2") (pin "13") (pinfunction "13_13") (pintype "passive"))
    )
    (net (code "94") (name "unconnected-(SV2-Pad15)") (class "Default")
      (node (ref "SV2") (pin "15") (pinfunction "15_15") (pintype "passive"))
    )
  )
)
